# SAM4S_MCU.net
KiCad netlist of a schematic drawn in Altium Designer
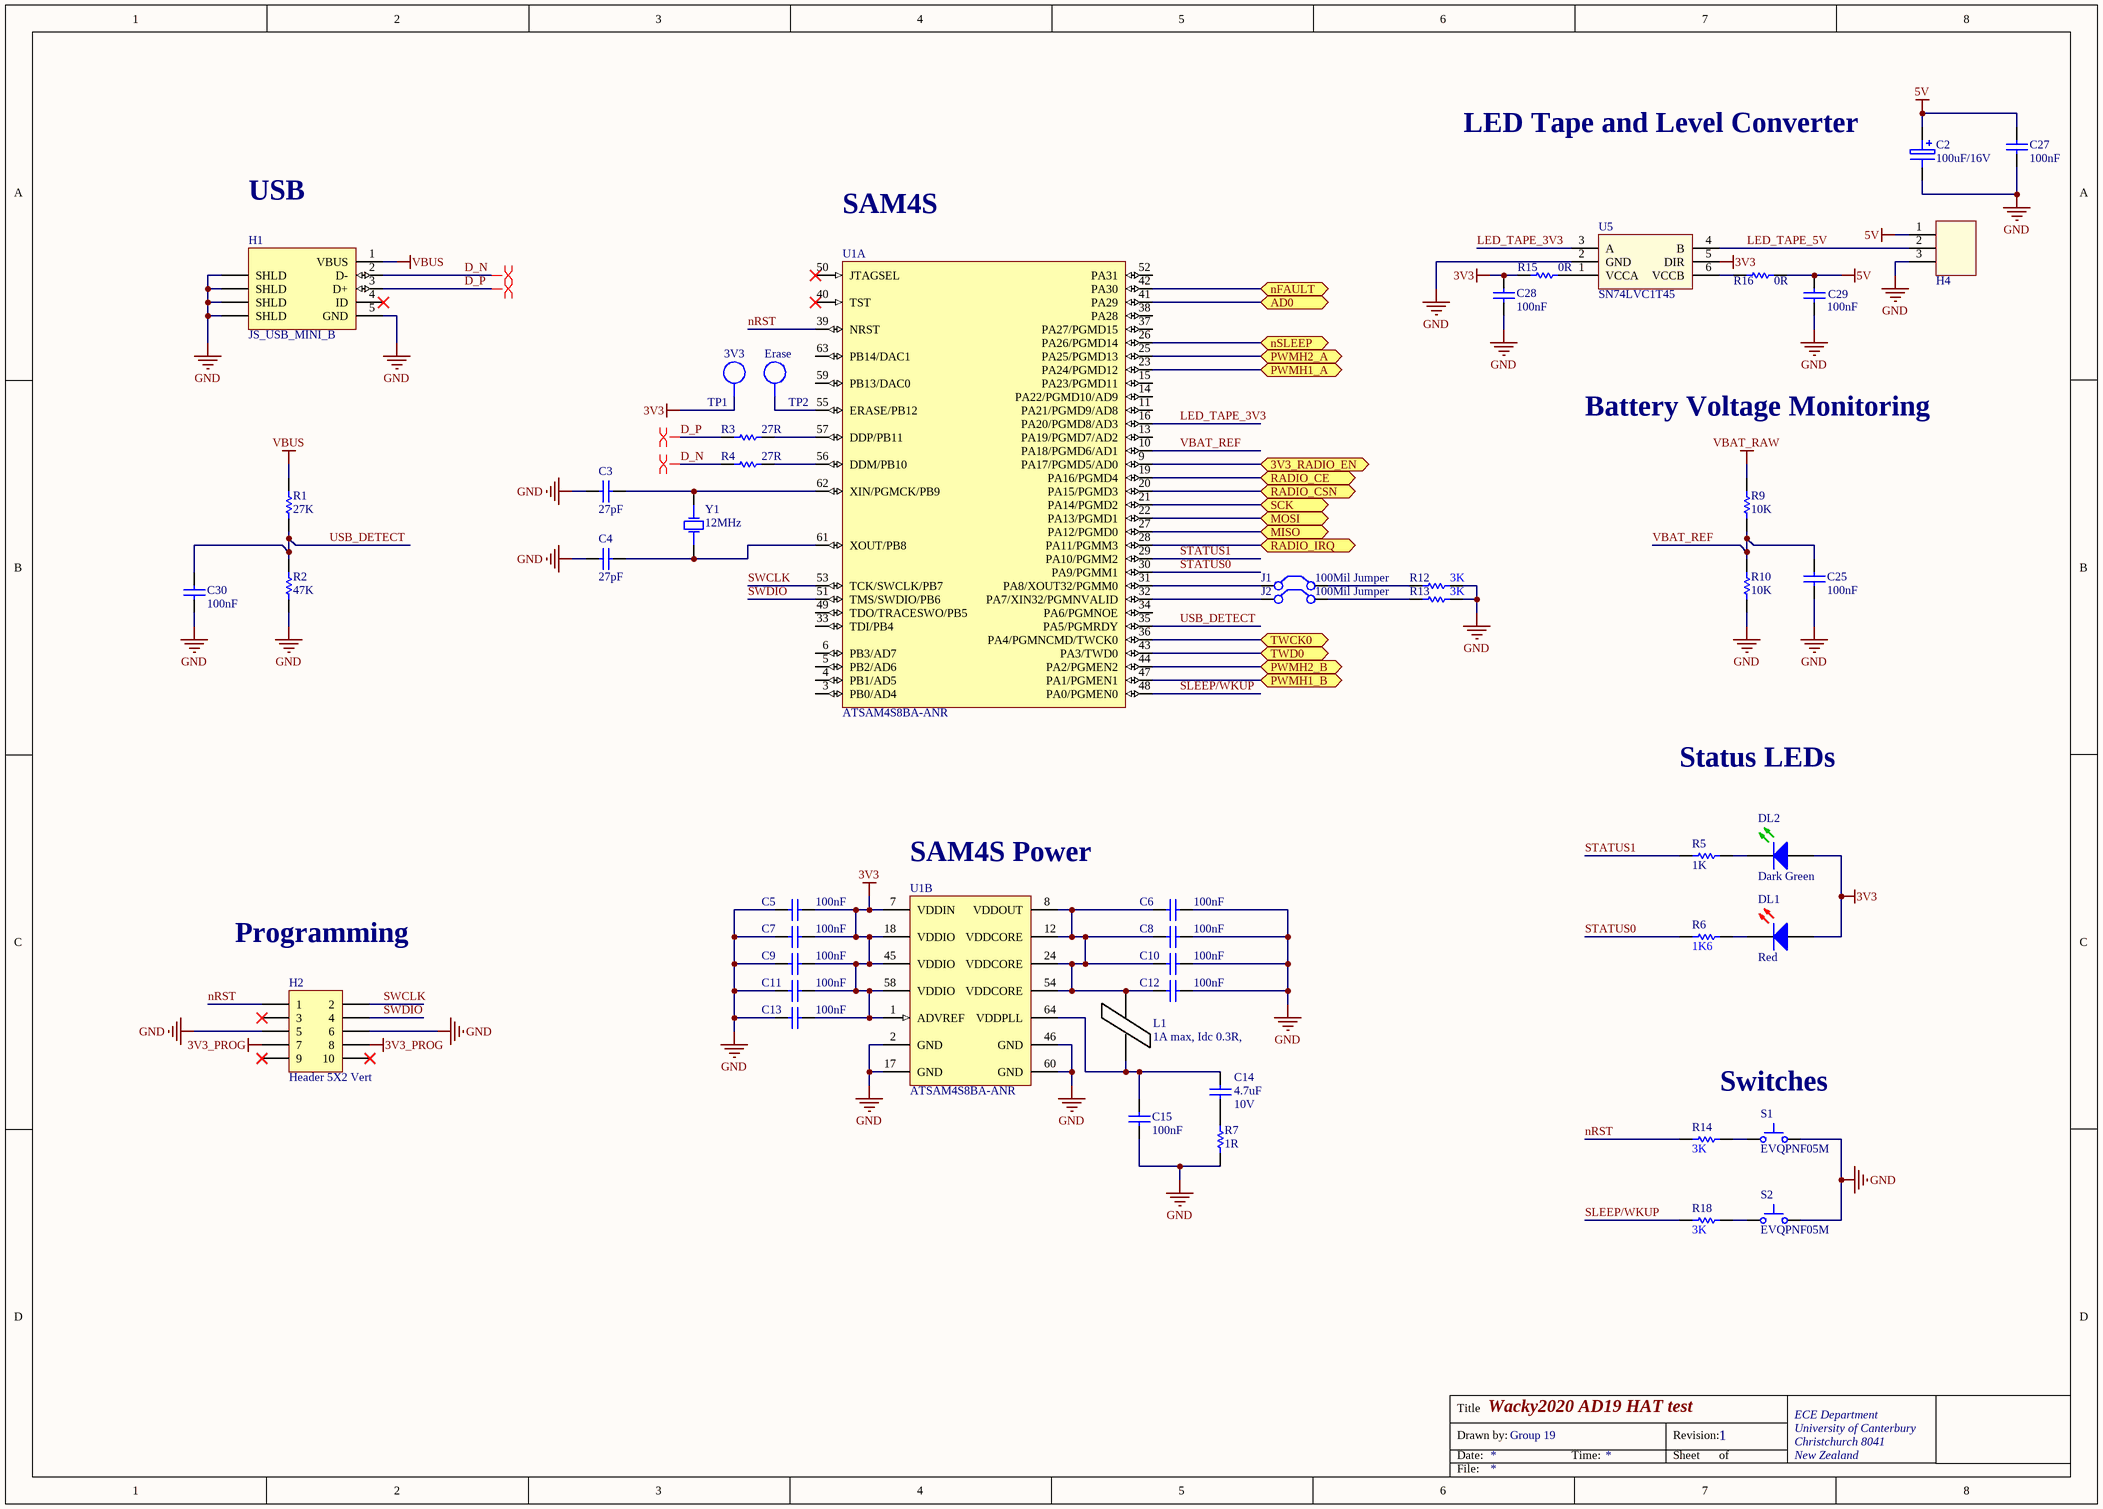
[diagram p0: SAM4S_MCU.SchDoc]

(export (version "E")
  (design (tool "Eeschema 10.0.6"))
  (components
    (comp (ref "C2")
      (value "100uF/16V")
      (footprint "NICH-1")
      (description "CAP ALUM 100uF 16V SMD")
      (fields (field (name "MANUFACTURER") "Nichcon"))
      (libsource (lib "ECE AD19Components_19V1") (part "CA_100uF_16V"))
    )
    (comp (ref "C3")
      (value "27pF")
      (footprint "CAPC1608L")
      (description "CAP CER 27pF NPO/COG +-5% 50V 0603")
      (libsource (lib "ECE AD19Components_19V1") (part "CC_27pF_0603"))
    )
    (comp (ref "C4")
      (value "27pF")
      (footprint "CAPC1608L")
      (description "CAP CER 27pF NPO/COG +-5% 50V 0603")
      (libsource (lib "ECE AD19Components_19V1") (part "CC_27pF_0603"))
    )
    (comp (ref "C5")
      (value "100nF")
      (footprint "CAPC1608L")
      (description "CAP CER 100nF X7R +-10% 50V 0603")
      (libsource (lib "ECE AD19Components_19V1") (part "CC_100nF_0603"))
    )
    (comp (ref "C6")
      (value "100nF")
      (footprint "CAPC1608L")
      (description "CAP CER 100nF X7R +-10% 50V 0603")
      (libsource (lib "ECE AD19Components_19V1") (part "CC_100nF_0603"))
    )
    (comp (ref "C7")
      (value "100nF")
      (footprint "CAPC1608L")
      (description "CAP CER 100nF X7R +-10% 50V 0603")
      (libsource (lib "ECE AD19Components_19V1") (part "CC_100nF_0603"))
    )
    (comp (ref "C8")
      (value "100nF")
      (footprint "CAPC1608L")
      (description "CAP CER 100nF X7R +-10% 50V 0603")
      (libsource (lib "ECE AD19Components_19V1") (part "CC_100nF_0603"))
    )
    (comp (ref "C9")
      (value "100nF")
      (footprint "CAPC1608L")
      (description "CAP CER 100nF X7R +-10% 50V 0603")
      (libsource (lib "ECE AD19Components_19V1") (part "CC_100nF_0603"))
    )
    (comp (ref "C10")
      (value "100nF")
      (footprint "CAPC1608L")
      (description "CAP CER 100nF X7R +-10% 50V 0603")
      (libsource (lib "ECE AD19Components_19V1") (part "CC_100nF_0603"))
    )
    (comp (ref "C11")
      (value "100nF")
      (footprint "CAPC1608L")
      (description "CAP CER 100nF X7R +-10% 50V 0603")
      (libsource (lib "ECE AD19Components_19V1") (part "CC_100nF_0603"))
    )
    (comp (ref "C12")
      (value "100nF")
      (footprint "CAPC1608L")
      (description "CAP CER 100nF X7R +-10% 50V 0603")
      (libsource (lib "ECE AD19Components_19V1") (part "CC_100nF_0603"))
    )
    (comp (ref "C13")
      (value "100nF")
      (footprint "CAPC1608L")
      (description "CAP CER 100nF X7R +-10% 50V 0603")
      (libsource (lib "ECE AD19Components_19V1") (part "CC_100nF_0603"))
    )
    (comp (ref "C14")
      (value "4.7uF")
      (footprint "CAPC1608N")
      (description "CAP CER 4.7uF X5R +-20%  10V 0603")
      (fields (field (name "MAX VOLTAGE") "10V"))
      (libsource (lib "ECE AD19Components_19V1") (part "CC_4.7uF_0603"))
    )
    (comp (ref "C15")
      (value "100nF")
      (footprint "CAPC1608L")
      (description "CAP CER 100nF X7R +-10% 50V 0603")
      (libsource (lib "ECE AD19Components_19V1") (part "CC_100nF_0603"))
    )
    (comp (ref "C25")
      (value "100nF")
      (footprint "CAPC1608L")
      (description "CAP CER 100nF X7R +-10% 50V 0603")
      (libsource (lib "ECE AD19Components_19V1") (part "CC_100nF_0603"))
    )
    (comp (ref "C27")
      (value "100nF")
      (footprint "CAPC1608L")
      (description "CAP CER 100nF X7R +-10% 50V 0603")
      (libsource (lib "ECE AD19Components_19V1") (part "CC_100nF_0603"))
    )
    (comp (ref "C28")
      (value "100nF")
      (footprint "CAPC1608L")
      (description "CAP CER 100nF X7R +-10% 50V 0603")
      (libsource (lib "ECE AD19Components_19V1") (part "CC_100nF_0603"))
    )
    (comp (ref "C29")
      (value "100nF")
      (footprint "CAPC1608L")
      (description "CAP CER 100nF X7R +-10% 50V 0603")
      (libsource (lib "ECE AD19Components_19V1") (part "CC_100nF_0603"))
    )
    (comp (ref "C30")
      (value "100nF")
      (footprint "CAPC1608L")
      (description "CAP CER 100nF X7R +-10% 50V 0603")
      (libsource (lib "ECE AD19Components_19V1") (part "CC_100nF_0603"))
    )
    (comp (ref "DL1")
      (value "Red")
      (footprint "WL-SMCW0603")
      (description "LED Red 250mcd 0603 SMD")
      (fields
        (field (name "MANUFACTURER") "WURTH ELEKTRONIK")
        (field (name "MANUFACTURER PART NUMBER") "150060RS75000")
        (field (name "LED COLOUR") "Red")
      )
      (libsource (lib "ECE AD19Components_19V1") (part "DL_150060RS75000"))
    )
    (comp (ref "DL2")
      (value "Dark Green")
      (footprint "WL-SMCW0603")
      (description "LED Dk Green 430mcd 0603 SMD")
      (fields
        (field (name "MANUFACTURER") "WURTH ELEKTRONIK")
        (field (name "MANUFACTURER PART NUMBER") "150060GS75000")
        (field (name "LED COLOUR") "Dark Green")
      )
      (libsource (lib "ECE AD19Components_19V1") (part "DL_150060GS75000"))
    )
    (comp (ref "H1")
      (value "JS_USB_MINI_B")
      (footprint "USB/SM0.8-6H5")
      (description "USB 2.0, Right Angle, SMT, B Type, Receptacle, 5 Position,")
      (fields (field (name "MANUFACTURER") "FCI"))
      (libsource (lib "ECE AD19Components_19V1") (part "JS_USB_MINI_B_SMT"))
    )
    (comp (ref "H2")
      (value "Header 5X2 Vert")
      (footprint "IDC2.54-V10D")
      (description "IDC Header, 2,54mm, 10-Pin, Vert")
      (libsource (lib "ECE AD19Components_19V1") (part "JA_HDR_IDC_5X2_VERT"))
    )
    (comp (ref "H4")
      (value "HEADER_3")
      (footprint "HEADER_3POS")
      (description "3Pin Header 2.54mm spacing")
      (libsource (lib "ENCE461AD19_19V2") (part "HEADER_3"))
    )
    (comp (ref "J1")
      (value "100Mil Jumper")
      (footprint "JMP2.54")
      (description "2.54mm Jumper Thru Hole")
      (libsource (lib "ECE AD19Components_19V1") (part "TP_JUMPER"))
    )
    (comp (ref "J2")
      (value "100Mil Jumper")
      (footprint "JMP2.54")
      (description "2.54mm Jumper Thru Hole")
      (libsource (lib "ECE AD19Components_19V1") (part "TP_JUMPER"))
    )
    (comp (ref "L1")
      (value "1A max, Idc 0.3R,")
      (footprint "INDC3216L")
      (description "Ferrite Bead, Rdc 0.3R, Z100MHZ 600R, Imax 1A, SMD 1206")
      (fields
        (field (name "MANUFACTURER") "FAIR-RITE")
        (field (name "MANUFACTURER PART NUMBER") "2512066017Y1")
      )
      (libsource (lib "ECE AD19Components_19V1") (part "IN_Ferrite-Bead"))
    )
    (comp (ref "R1")
      (value "27K")
      (footprint "RESC1608L")
      (description "RES 27K OHM 1/10W 5% 0603 SMD")
      (libsource (lib "ECE AD19Components_19V1") (part "RS_27K"))
    )
    (comp (ref "R2")
      (value "47K")
      (footprint "RESC1608N")
      (description "RES 47.0K OHM 1/10W 5% 0603 SMD")
      (libsource (lib "ECE AD19Components_19V1") (part "RS_47K"))
    )
    (comp (ref "R3")
      (value "27R")
      (footprint "RESC1608L")
      (description "RES 27 OHM 1/10W 5% 0603 SMD")
      (libsource (lib "ECE AD19Components_19V1") (part "RS_27R"))
    )
    (comp (ref "R4")
      (value "27R")
      (footprint "RESC1608L")
      (description "RES 27 OHM 1/10W 5% 0603 SMD")
      (libsource (lib "ECE AD19Components_19V1") (part "RS_27R"))
    )
    (comp (ref "R5")
      (value "1K")
      (footprint "RESC1608L")
      (description "RES 1.0K OHM 1/10W 5% 0603 SMD")
      (libsource (lib "ECE AD19Components_19V1") (part "RS_1K"))
    )
    (comp (ref "R6")
      (value "1K6")
      (footprint "RESC1608L")
      (description "RES 1.6K OHM 1/10W 5% 0603 SMD")
      (libsource (lib "ECE AD19Components_19V1") (part "RS_1K6"))
    )
    (comp (ref "R7")
      (value "1R")
      (footprint "RESC3216L")
      (description "RES 1R OHM 1/4W 5% 1206 SMD")
      (libsource (lib "ECE AD19Components_19V1") (part "RT_1R"))
    )
    (comp (ref "R9")
      (value "10K")
      (footprint "RESC1608L")
      (description "RES 10.0K OHM 1/10W 5% 0603 SMD")
      (libsource (lib "ECE AD19Components_19V1") (part "RS_10K"))
    )
    (comp (ref "R10")
      (value "10K")
      (footprint "RESC1608L")
      (description "RES 10.0K OHM 1/10W 5% 0603 SMD")
      (libsource (lib "ECE AD19Components_19V1") (part "RS_10K"))
    )
    (comp (ref "R12")
      (value "3K")
      (footprint "RESC1608L")
      (description "RES 3K OHM 1/10W 5% 0603 SMD")
      (libsource (lib "ECE AD19Components_19V1") (part "RS_3K"))
    )
    (comp (ref "R13")
      (value "3K")
      (footprint "RESC1608L")
      (description "RES 3K OHM 1/10W 5% 0603 SMD")
      (libsource (lib "ECE AD19Components_19V1") (part "RS_3K"))
    )
    (comp (ref "R14")
      (value "3K")
      (footprint "RESC1608L")
      (description "RES 3K OHM 1/10W 5% 0603 SMD")
      (libsource (lib "ECE AD19Components_19V1") (part "RS_3K"))
    )
    (comp (ref "R15")
      (value "0R")
      (footprint "RESC1608L")
      (description "RES 0.0 OHM 1/10W 5% 0603 SMD")
      (libsource (lib "ECE AD19Components_19V1") (part "RS_0R0"))
    )
    (comp (ref "R16")
      (value "0R")
      (footprint "RESC1608L")
      (description "RES 0.0 OHM 1/10W 5% 0603 SMD")
      (libsource (lib "ECE AD19Components_19V1") (part "RS_0R0"))
    )
    (comp (ref "R18")
      (value "3K")
      (footprint "RESC1608L")
      (description "RES 3K OHM 1/10W 5% 0603 SMD")
      (libsource (lib "ECE AD19Components_19V1") (part "RS_3K"))
    )
    (comp (ref "S1")
      (value "EVQPNF05M")
      (footprint "EVQPNF05M")
      (description "Panasonic 6 x 3.5mm SMD Light Touch Switch Type SMD")
      (fields (field (name "MANUFACTURER") "Panasonic"))
      (libsource (lib "ECE AD19Components_19V1") (part "WS_EVQPNF05M"))
    )
    (comp (ref "S2")
      (value "EVQPNF05M")
      (footprint "EVQPNF05M")
      (description "Panasonic 6 x 3.5mm SMD Light Touch Switch Type SMD")
      (fields (field (name "MANUFACTURER") "Panasonic"))
      (libsource (lib "ECE AD19Components_19V1") (part "WS_EVQPNF05M"))
    )
    (comp (ref "TP1")
      (value "3V3")
      (footprint "TP_1206")
      (description "Test-Point 3.3x1.6x2.1mm SMD")
      (fields
        (field (name "MANUFACTURER") "Harwin Inc")
        (field (name "MANUFACTURER PART NUMBER") "S1751-46R")
      )
      (libsource (lib "ECE AD19Components_19V1") (part "TP_1206"))
    )
    (comp (ref "TP2")
      (value "Erase")
      (footprint "TP_1206")
      (description "Test-Point 3.3x1.6x2.1mm SMD")
      (fields
        (field (name "MANUFACTURER") "Harwin Inc")
        (field (name "MANUFACTURER PART NUMBER") "S1751-46R")
      )
      (libsource (lib "ECE AD19Components_19V1") (part "TP_1206"))
    )
    (comp (ref "U1")
      (value "ATSAM4S8BA-ANR")
      (footprint "LQFP64_L")
      (description "IC MCU 32BIT 512KB FLASH 64LQFP")
      (fields (field (name "MANUFACTURER") "Atmel"))
      (libsource (lib "ECE AD19Components_19V1") (part "SE_ATSAM4S16BA-MU"))
    )
    (comp (ref "U5")
      (value "SN74LVC1T45")
      (footprint "SOT23-6_N")
      (description "1.8V - 5V level converter")
      (libsource (lib "ENCE461_extras_2020") (part "SN74LVC1T45"))
    )
    (comp (ref "Y1")
      (value "12MHz")
      (footprint "6.0X3.5-4")
      (description "CRYSTAL 12MHZ 18PF 6X3.5mm SMD")
      (fields
        (field (name "MANUFACTURER") "CTS-Frequency Controls")
        (field (name "MANUFACTURER PART NUMBER") "406C35D12M00000")
        (field (name "FREQUENCY") "12MHz")
      )
      (libsource (lib "ECE AD19Components_19V1") (part "XT_CRYSTAL_12MHz_18pF"))
    )
  )
  (nets
    (net (code "1") (name "/3V3_RADIO_EN") (class "Default")
      (node (ref "U1") (pin "9") (pinfunction "PA17/PGMD5/AD0_9") (pintype "bidirectional"))
    )
    (net (code "2") (name "/AD0") (class "Default")
      (node (ref "U1") (pin "41") (pinfunction "PA29_41") (pintype "bidirectional"))
    )
    (net (code "3") (name "/D_N") (class "Default")
      (node (ref "H1") (pin "2") (pinfunction "D-_2") (pintype "bidirectional"))
      (node (ref "R4") (pin "1") (pinfunction "1_1") (pintype "passive"))
    )
    (net (code "4") (name "/D_P") (class "Default")
      (node (ref "H1") (pin "3") (pinfunction "D+_3") (pintype "bidirectional"))
      (node (ref "R3") (pin "1") (pinfunction "1_1") (pintype "passive"))
    )
    (net (code "5") (name "/LED_TAPE_3V3") (class "Default")
      (node (ref "U1") (pin "16") (pinfunction "PA20/PGMD8/AD3_16") (pintype "bidirectional"))
      (node (ref "U5") (pin "3") (pinfunction "A_3") (pintype "passive"))
    )
    (net (code "6") (name "/LED_TAPE_5V") (class "Default")
      (node (ref "H4") (pin "2") (pintype "passive"))
      (node (ref "U5") (pin "4") (pinfunction "B_4") (pintype "passive"))
    )
    (net (code "7") (name "/MISO") (class "Default")
      (node (ref "U1") (pin "27") (pinfunction "PA12/PGMD0_27") (pintype "bidirectional"))
    )
    (net (code "8") (name "/MOSI") (class "Default")
      (node (ref "U1") (pin "22") (pinfunction "PA13/PGMD1_22") (pintype "bidirectional"))
    )
    (net (code "9") (name "/PWMH1_A") (class "Default")
      (node (ref "U1") (pin "23") (pinfunction "PA24/PGMD12_23") (pintype "bidirectional"))
    )
    (net (code "10") (name "/PWMH1_B") (class "Default")
      (node (ref "U1") (pin "47") (pinfunction "PA1/PGMEN1_47") (pintype "bidirectional"))
    )
    (net (code "11") (name "/PWMH2_A") (class "Default")
      (node (ref "U1") (pin "25") (pinfunction "PA25/PGMD13_25") (pintype "bidirectional"))
    )
    (net (code "12") (name "/PWMH2_B") (class "Default")
      (node (ref "U1") (pin "44") (pinfunction "PA2/PGMEN2_44") (pintype "bidirectional"))
    )
    (net (code "13") (name "/RADIO_CE") (class "Default")
      (node (ref "U1") (pin "19") (pinfunction "PA16/PGMD4_19") (pintype "bidirectional"))
    )
    (net (code "14") (name "/RADIO_CSN") (class "Default")
      (node (ref "U1") (pin "20") (pinfunction "PA15/PGMD3_20") (pintype "bidirectional"))
    )
    (net (code "15") (name "/RADIO_IRQ") (class "Default")
      (node (ref "U1") (pin "28") (pinfunction "PA11/PGMM3_28") (pintype "bidirectional"))
    )
    (net (code "16") (name "/SCK") (class "Default")
      (node (ref "U1") (pin "21") (pinfunction "PA14/PGMD2_21") (pintype "bidirectional"))
    )
    (net (code "17") (name "/SLEEP{slash}WKUP") (class "Default")
      (node (ref "R18") (pin "1") (pinfunction "1_1") (pintype "passive"))
      (node (ref "U1") (pin "48") (pinfunction "PA0/PGMEN0_48") (pintype "bidirectional"))
    )
    (net (code "18") (name "/STATUS0") (class "Default")
      (node (ref "R6") (pin "1") (pinfunction "1_1") (pintype "passive"))
      (node (ref "U1") (pin "30") (pinfunction "PA9/PGMM1_30") (pintype "bidirectional"))
    )
    (net (code "19") (name "/STATUS1") (class "Default")
      (node (ref "R5") (pin "1") (pinfunction "1_1") (pintype "passive"))
      (node (ref "U1") (pin "29") (pinfunction "PA10/PGMM2_29") (pintype "bidirectional"))
    )
    (net (code "20") (name "/SWCLK") (class "Default")
      (node (ref "H2") (pin "2") (pinfunction "2_2") (pintype "passive"))
      (node (ref "U1") (pin "53") (pinfunction "TCK/SWCLK/PB7_53") (pintype "bidirectional"))
    )
    (net (code "21") (name "/SWDIO") (class "Default")
      (node (ref "H2") (pin "4") (pinfunction "4_4") (pintype "passive"))
      (node (ref "U1") (pin "51") (pinfunction "TMS/SWDIO/PB6_51") (pintype "bidirectional"))
    )
    (net (code "22") (name "/TWCK0") (class "Default")
      (node (ref "U1") (pin "36") (pinfunction "PA4/PGMNCMD/TWCK0_36") (pintype "bidirectional"))
    )
    (net (code "23") (name "/TWD0") (class "Default")
      (node (ref "U1") (pin "43") (pinfunction "PA3/TWD0_43") (pintype "bidirectional"))
    )
    (net (code "24") (name "/USB_DETECT") (class "Default")
      (node (ref "C30") (pin "2") (pinfunction "2_2") (pintype "passive"))
      (node (ref "R1") (pin "1") (pinfunction "1_1") (pintype "passive"))
      (node (ref "R2") (pin "2") (pinfunction "2_2") (pintype "passive"))
      (node (ref "U1") (pin "35") (pinfunction "PA5/PGMRDY_35") (pintype "bidirectional"))
    )
    (net (code "25") (name "/VBAT_REF") (class "Default")
      (node (ref "C25") (pin "2") (pinfunction "2_2") (pintype "passive"))
      (node (ref "R10") (pin "2") (pinfunction "2_2") (pintype "passive"))
      (node (ref "R9") (pin "1") (pinfunction "1_1") (pintype "passive"))
      (node (ref "U1") (pin "10") (pinfunction "PA18/PGMD6/AD1_10") (pintype "bidirectional"))
    )
    (net (code "26") (name "/nFAULT") (class "Default")
      (node (ref "U1") (pin "42") (pinfunction "PA30_42") (pintype "bidirectional"))
    )
    (net (code "27") (name "/nRST") (class "Default")
      (node (ref "H2") (pin "1") (pinfunction "1_1") (pintype "passive"))
      (node (ref "R14") (pin "1") (pinfunction "1_1") (pintype "passive"))
      (node (ref "U1") (pin "39") (pinfunction "NRST_39") (pintype "bidirectional"))
    )
    (net (code "28") (name "/nSLEEP") (class "Default")
      (node (ref "U1") (pin "26") (pinfunction "PA26/PGMD14_26") (pintype "bidirectional"))
    )
    (net (code "29") (name "3V3") (class "Default")
      (node (ref "C11") (pin "2") (pinfunction "2_2") (pintype "passive"))
      (node (ref "C13") (pin "2") (pinfunction "2_2") (pintype "passive"))
      (node (ref "C28") (pin "2") (pinfunction "2_2") (pintype "passive"))
      (node (ref "C5") (pin "2") (pinfunction "2_2") (pintype "passive"))
      (node (ref "C7") (pin "2") (pinfunction "2_2") (pintype "passive"))
      (node (ref "C9") (pin "2") (pinfunction "2_2") (pintype "passive"))
      (node (ref "DL1") (pin "2") (pinfunction "A_2") (pintype "passive"))
      (node (ref "DL2") (pin "2") (pinfunction "A_2") (pintype "passive"))
      (node (ref "R15") (pin "1") (pinfunction "1_1") (pintype "passive"))
      (node (ref "TP1") (pin "1") (pinfunction "1_1") (pintype "passive"))
      (node (ref "U1") (pin "1") (pinfunction "ADVREF_1") (pintype "input"))
      (node (ref "U1") (pin "18") (pinfunction "VDDIO_18") (pintype "power_in"))
      (node (ref "U1") (pin "45") (pinfunction "VDDIO_45") (pintype "power_in"))
      (node (ref "U1") (pin "58") (pinfunction "VDDIO_58") (pintype "power_in"))
      (node (ref "U1") (pin "7") (pinfunction "VDDIN_7") (pintype "power_in"))
      (node (ref "U5") (pin "5") (pinfunction "DIR_5") (pintype "passive"))
    )
    (net (code "30") (name "3V3_PROG") (class "Default")
      (node (ref "H2") (pin "7") (pinfunction "7_7") (pintype "passive"))
      (node (ref "H2") (pin "8") (pinfunction "8_8") (pintype "passive"))
    )
    (net (code "31") (name "5V") (class "Default")
      (node (ref "C2") (pin "2") (pintype "passive"))
      (node (ref "C27") (pin "2") (pinfunction "2_2") (pintype "passive"))
      (node (ref "C29") (pin "2") (pinfunction "2_2") (pintype "passive"))
      (node (ref "H4") (pin "1") (pintype "passive"))
      (node (ref "R16") (pin "2") (pinfunction "2_2") (pintype "passive"))
    )
    (net (code "32") (name "GND") (class "Default")
      (node (ref "C10") (pin "2") (pinfunction "2_2") (pintype "passive"))
      (node (ref "C11") (pin "1") (pinfunction "1_1") (pintype "passive"))
      (node (ref "C12") (pin "2") (pinfunction "2_2") (pintype "passive"))
      (node (ref "C13") (pin "1") (pinfunction "1_1") (pintype "passive"))
      (node (ref "C15") (pin "2") (pinfunction "2_2") (pintype "passive"))
      (node (ref "C2") (pin "1") (pintype "passive"))
      (node (ref "C25") (pin "1") (pinfunction "1_1") (pintype "passive"))
      (node (ref "C27") (pin "1") (pinfunction "1_1") (pintype "passive"))
      (node (ref "C28") (pin "1") (pinfunction "1_1") (pintype "passive"))
      (node (ref "C29") (pin "1") (pinfunction "1_1") (pintype "passive"))
      (node (ref "C3") (pin "1") (pinfunction "1_1") (pintype "passive"))
      (node (ref "C30") (pin "1") (pinfunction "1_1") (pintype "passive"))
      (node (ref "C4") (pin "1") (pinfunction "1_1") (pintype "passive"))
      (node (ref "C5") (pin "1") (pinfunction "1_1") (pintype "passive"))
      (node (ref "C6") (pin "2") (pinfunction "2_2") (pintype "passive"))
      (node (ref "C7") (pin "1") (pinfunction "1_1") (pintype "passive"))
      (node (ref "C8") (pin "2") (pinfunction "2_2") (pintype "passive"))
      (node (ref "C9") (pin "1") (pinfunction "1_1") (pintype "passive"))
      (node (ref "H1") (pin "5") (pinfunction "GND_5") (pintype "passive"))
      (node (ref "H1") (pin "6") (pinfunction "SHLD_6") (pintype "passive"))
      (node (ref "H1") (pin "7") (pinfunction "SHLD_7") (pintype "passive"))
      (node (ref "H1") (pin "8") (pinfunction "SHLD_8") (pintype "passive"))
      (node (ref "H1") (pin "9") (pinfunction "SHLD_9") (pintype "passive"))
      (node (ref "H2") (pin "5") (pinfunction "5_5") (pintype "passive"))
      (node (ref "H2") (pin "6") (pinfunction "6_6") (pintype "passive"))
      (node (ref "H4") (pin "3") (pintype "passive"))
      (node (ref "R10") (pin "1") (pinfunction "1_1") (pintype "passive"))
      (node (ref "R12") (pin "2") (pinfunction "2_2") (pintype "passive"))
      (node (ref "R13") (pin "2") (pinfunction "2_2") (pintype "passive"))
      (node (ref "R2") (pin "1") (pinfunction "1_1") (pintype "passive"))
      (node (ref "R7") (pin "1") (pinfunction "1_1") (pintype "passive"))
      (node (ref "S1") (pin "1") (pintype "passive"))
      (node (ref "S2") (pin "1") (pintype "passive"))
      (node (ref "U1") (pin "17") (pinfunction "GND_17") (pintype "power_in"))
      (node (ref "U1") (pin "2") (pinfunction "GND_2") (pintype "power_in"))
      (node (ref "U1") (pin "46") (pinfunction "GND_46") (pintype "power_in"))
      (node (ref "U1") (pin "60") (pinfunction "GND_60") (pintype "power_in"))
      (node (ref "U5") (pin "2") (pinfunction "GND_2") (pintype "passive"))
    )
    (net (code "33") (name "Net-(C14-Pad1)") (class "Default")
      (node (ref "C14") (pin "1") (pinfunction "1_1") (pintype "passive"))
      (node (ref "R7") (pin "2") (pinfunction "2_2") (pintype "passive"))
    )
    (net (code "34") (name "Net-(DL1-K)") (class "Default")
      (node (ref "DL1") (pin "1") (pinfunction "K_1") (pintype "passive"))
      (node (ref "R6") (pin "2") (pinfunction "2_2") (pintype "passive"))
    )
    (net (code "35") (name "Net-(DL2-K)") (class "Default")
      (node (ref "DL2") (pin "1") (pinfunction "K_1") (pintype "passive"))
      (node (ref "R5") (pin "2") (pinfunction "2_2") (pintype "passive"))
    )
    (net (code "36") (name "Net-(J1-C1)") (class "Default")
      (node (ref "J1") (pin "1") (pinfunction "C1_1") (pintype "passive"))
      (node (ref "U1") (pin "31") (pinfunction "PA8/XOUT32/PGMM0_31") (pintype "bidirectional"))
    )
    (net (code "37") (name "Net-(J1-C2)") (class "Default")
      (node (ref "J1") (pin "2") (pinfunction "C2_2") (pintype "passive"))
      (node (ref "R12") (pin "1") (pinfunction "1_1") (pintype "passive"))
    )
    (net (code "38") (name "Net-(J2-C1)") (class "Default")
      (node (ref "J2") (pin "1") (pinfunction "C1_1") (pintype "passive"))
      (node (ref "U1") (pin "32") (pinfunction "PA7/XIN32/PGMNVALID_32") (pintype "bidirectional"))
    )
    (net (code "39") (name "Net-(J2-C2)") (class "Default")
      (node (ref "J2") (pin "2") (pinfunction "C2_2") (pintype "passive"))
      (node (ref "R13") (pin "1") (pinfunction "1_1") (pintype "passive"))
    )
    (net (code "40") (name "Net-(R14-Pad2)") (class "Default")
      (node (ref "R14") (pin "2") (pinfunction "2_2") (pintype "passive"))
      (node (ref "S1") (pin "2") (pintype "passive"))
    )
    (net (code "41") (name "Net-(R18-Pad2)") (class "Default")
      (node (ref "R18") (pin "2") (pinfunction "2_2") (pintype "passive"))
      (node (ref "S2") (pin "2") (pintype "passive"))
    )
    (net (code "42") (name "Net-(U1A-DDM{slash}PB10)") (class "Default")
      (node (ref "R4") (pin "2") (pinfunction "2_2") (pintype "passive"))
      (node (ref "U1") (pin "56") (pinfunction "DDM/PB10_56") (pintype "bidirectional"))
    )
    (net (code "43") (name "Net-(U1A-DDP{slash}PB11)") (class "Default")
      (node (ref "R3") (pin "2") (pinfunction "2_2") (pintype "passive"))
      (node (ref "U1") (pin "57") (pinfunction "DDP/PB11_57") (pintype "bidirectional"))
    )
    (net (code "44") (name "Net-(U1A-ERASE{slash}PB12)") (class "Default")
      (node (ref "TP2") (pin "1") (pinfunction "1_1") (pintype "passive"))
      (node (ref "U1") (pin "55") (pinfunction "ERASE/PB12_55") (pintype "bidirectional"))
    )
    (net (code "45") (name "Net-(U1A-XIN{slash}PGMCK{slash}PB9)") (class "Default")
      (node (ref "C3") (pin "2") (pinfunction "2_2") (pintype "passive"))
      (node (ref "U1") (pin "62") (pinfunction "XIN/PGMCK/PB9_62") (pintype "bidirectional"))
      (node (ref "Y1") (pin "3") (pinfunction "OSC2_3") (pintype "passive"))
    )
    (net (code "46") (name "Net-(U1A-XOUT{slash}PB8)") (class "Default")
      (node (ref "C4") (pin "2") (pinfunction "2_2") (pintype "passive"))
      (node (ref "U1") (pin "61") (pinfunction "XOUT/PB8_61") (pintype "bidirectional"))
      (node (ref "Y1") (pin "1") (pinfunction "OSC1_1") (pintype "passive"))
    )
    (net (code "47") (name "Net-(U1B-VDDOUT)") (class "Default")
      (node (ref "C10") (pin "1") (pinfunction "1_1") (pintype "passive"))
      (node (ref "C12") (pin "1") (pinfunction "1_1") (pintype "passive"))
      (node (ref "C6") (pin "1") (pinfunction "1_1") (pintype "passive"))
      (node (ref "C8") (pin "1") (pinfunction "1_1") (pintype "passive"))
      (node (ref "L1") (pin "2") (pinfunction "2_2") (pintype "passive"))
      (node (ref "U1") (pin "12") (pinfunction "VDDCORE_12") (pintype "power_in"))
      (node (ref "U1") (pin "24") (pinfunction "VDDCORE_24") (pintype "power_in"))
      (node (ref "U1") (pin "54") (pinfunction "VDDCORE_54") (pintype "power_in"))
      (node (ref "U1") (pin "8") (pinfunction "VDDOUT_8") (pintype "power_in"))
    )
    (net (code "48") (name "Net-(U1B-VDDPLL)") (class "Default")
      (node (ref "C14") (pin "2") (pinfunction "2_2") (pintype "passive"))
      (node (ref "C15") (pin "1") (pinfunction "1_1") (pintype "passive"))
      (node (ref "L1") (pin "1") (pinfunction "1_1") (pintype "passive"))
      (node (ref "U1") (pin "64") (pinfunction "VDDPLL_64") (pintype "power_in"))
    )
    (net (code "49") (name "Net-(U5-VCCA)") (class "Default")
      (node (ref "R15") (pin "2") (pinfunction "2_2") (pintype "passive"))
      (node (ref "U5") (pin "1") (pinfunction "VCCA_1") (pintype "passive"))
    )
    (net (code "50") (name "Net-(U5-VCCB)") (class "Default")
      (node (ref "R16") (pin "1") (pinfunction "1_1") (pintype "passive"))
      (node (ref "U5") (pin "6") (pinfunction "VCCB_6") (pintype "passive"))
    )
    (net (code "51") (name "VBAT_RAW") (class "Default")
      (node (ref "R9") (pin "2") (pinfunction "2_2") (pintype "passive"))
    )
    (net (code "52") (name "VBUS") (class "Default")
      (node (ref "H1") (pin "1") (pinfunction "VBUS_1") (pintype "power_in"))
      (node (ref "R1") (pin "2") (pinfunction "2_2") (pintype "passive"))
    )
    (net (code "53") (name "unconnected-(H1-ID-Pad4)") (class "Default")
      (node (ref "H1") (pin "4") (pinfunction "ID_4") (pintype "power_in+no_connect"))
    )
    (net (code "54") (name "unconnected-(H2-Pad3)") (class "Default")
      (node (ref "H2") (pin "3") (pinfunction "3_3") (pintype "passive+no_connect"))
    )
    (net (code "55") (name "unconnected-(H2-Pad9)") (class "Default")
      (node (ref "H2") (pin "9") (pinfunction "9_9") (pintype "passive+no_connect"))
    )
    (net (code "56") (name "unconnected-(H2-Pad10)") (class "Default")
      (node (ref "H2") (pin "10") (pinfunction "10_10") (pintype "passive+no_connect"))
    )
    (net (code "57") (name "unconnected-(U1A-JTAGSEL-Pad50)") (class "Default")
      (node (ref "U1") (pin "50") (pinfunction "JTAGSEL_50") (pintype "input+no_connect"))
    )
    (net (code "58") (name "unconnected-(U1A-PA6{slash}PGMNOE-Pad34)") (class "Default")
      (node (ref "U1") (pin "34") (pinfunction "PA6/PGMNOE_34") (pintype "bidirectional"))
    )
    (net (code "59") (name "unconnected-(U1A-PA19{slash}PGMD7{slash}AD2-Pad13)") (class "Default")
      (node (ref "U1") (pin "13") (pinfunction "PA19/PGMD7/AD2_13") (pintype "bidirectional"))
    )
    (net (code "60") (name "unconnected-(U1A-PA21{slash}PGMD9{slash}AD8-Pad11)") (class "Default")
      (node (ref "U1") (pin "11") (pinfunction "PA21/PGMD9/AD8_11") (pintype "bidirectional"))
    )
    (net (code "61") (name "unconnected-(U1A-PA22{slash}PGMD10{slash}AD9-Pad14)") (class "Default")
      (node (ref "U1") (pin "14") (pinfunction "PA22/PGMD10/AD9_14") (pintype "bidirectional"))
    )
    (net (code "62") (name "unconnected-(U1A-PA23{slash}PGMD11-Pad15)") (class "Default")
      (node (ref "U1") (pin "15") (pinfunction "PA23/PGMD11_15") (pintype "bidirectional"))
    )
    (net (code "63") (name "unconnected-(U1A-PA27{slash}PGMD15-Pad37)") (class "Default")
      (node (ref "U1") (pin "37") (pinfunction "PA27/PGMD15_37") (pintype "bidirectional"))
    )
    (net (code "64") (name "unconnected-(U1A-PA28-Pad38)") (class "Default")
      (node (ref "U1") (pin "38") (pinfunction "PA28_38") (pintype "bidirectional"))
    )
    (net (code "65") (name "unconnected-(U1A-PA31-Pad52)") (class "Default")
      (node (ref "U1") (pin "52") (pinfunction "PA31_52") (pintype "bidirectional"))
    )
    (net (code "66") (name "unconnected-(U1A-PB0{slash}AD4-Pad3)") (class "Default")
      (node (ref "U1") (pin "3") (pinfunction "PB0/AD4_3") (pintype "bidirectional"))
    )
    (net (code "67") (name "unconnected-(U1A-PB1{slash}AD5-Pad4)") (class "Default")
      (node (ref "U1") (pin "4") (pinfunction "PB1/AD5_4") (pintype "bidirectional"))
    )
    (net (code "68") (name "unconnected-(U1A-PB2{slash}AD6-Pad5)") (class "Default")
      (node (ref "U1") (pin "5") (pinfunction "PB2/AD6_5") (pintype "bidirectional"))
    )
    (net (code "69") (name "unconnected-(U1A-PB3{slash}AD7-Pad6)") (class "Default")
      (node (ref "U1") (pin "6") (pinfunction "PB3/AD7_6") (pintype "bidirectional"))
    )
    (net (code "70") (name "unconnected-(U1A-PB13{slash}DAC0-Pad59)") (class "Default")
      (node (ref "U1") (pin "59") (pinfunction "PB13/DAC0_59") (pintype "bidirectional"))
    )
    (net (code "71") (name "unconnected-(U1A-PB14{slash}DAC1-Pad63)") (class "Default")
      (node (ref "U1") (pin "63") (pinfunction "PB14/DAC1_63") (pintype "bidirectional"))
    )
    (net (code "72") (name "unconnected-(U1A-TDI{slash}PB4-Pad33)") (class "Default")
      (node (ref "U1") (pin "33") (pinfunction "TDI/PB4_33") (pintype "bidirectional"))
    )
    (net (code "73") (name "unconnected-(U1A-TDO{slash}TRACESWO{slash}PB5-Pad49)") (class "Default")
      (node (ref "U1") (pin "49") (pinfunction "TDO/TRACESWO/PB5_49") (pintype "bidirectional"))
    )
    (net (code "74") (name "unconnected-(U1A-TST-Pad40)") (class "Default")
      (node (ref "U1") (pin "40") (pinfunction "TST_40") (pintype "input+no_connect"))
    )
  )
)
